# main.net
KiCad netlist of a schematic drawn in Altium Designer
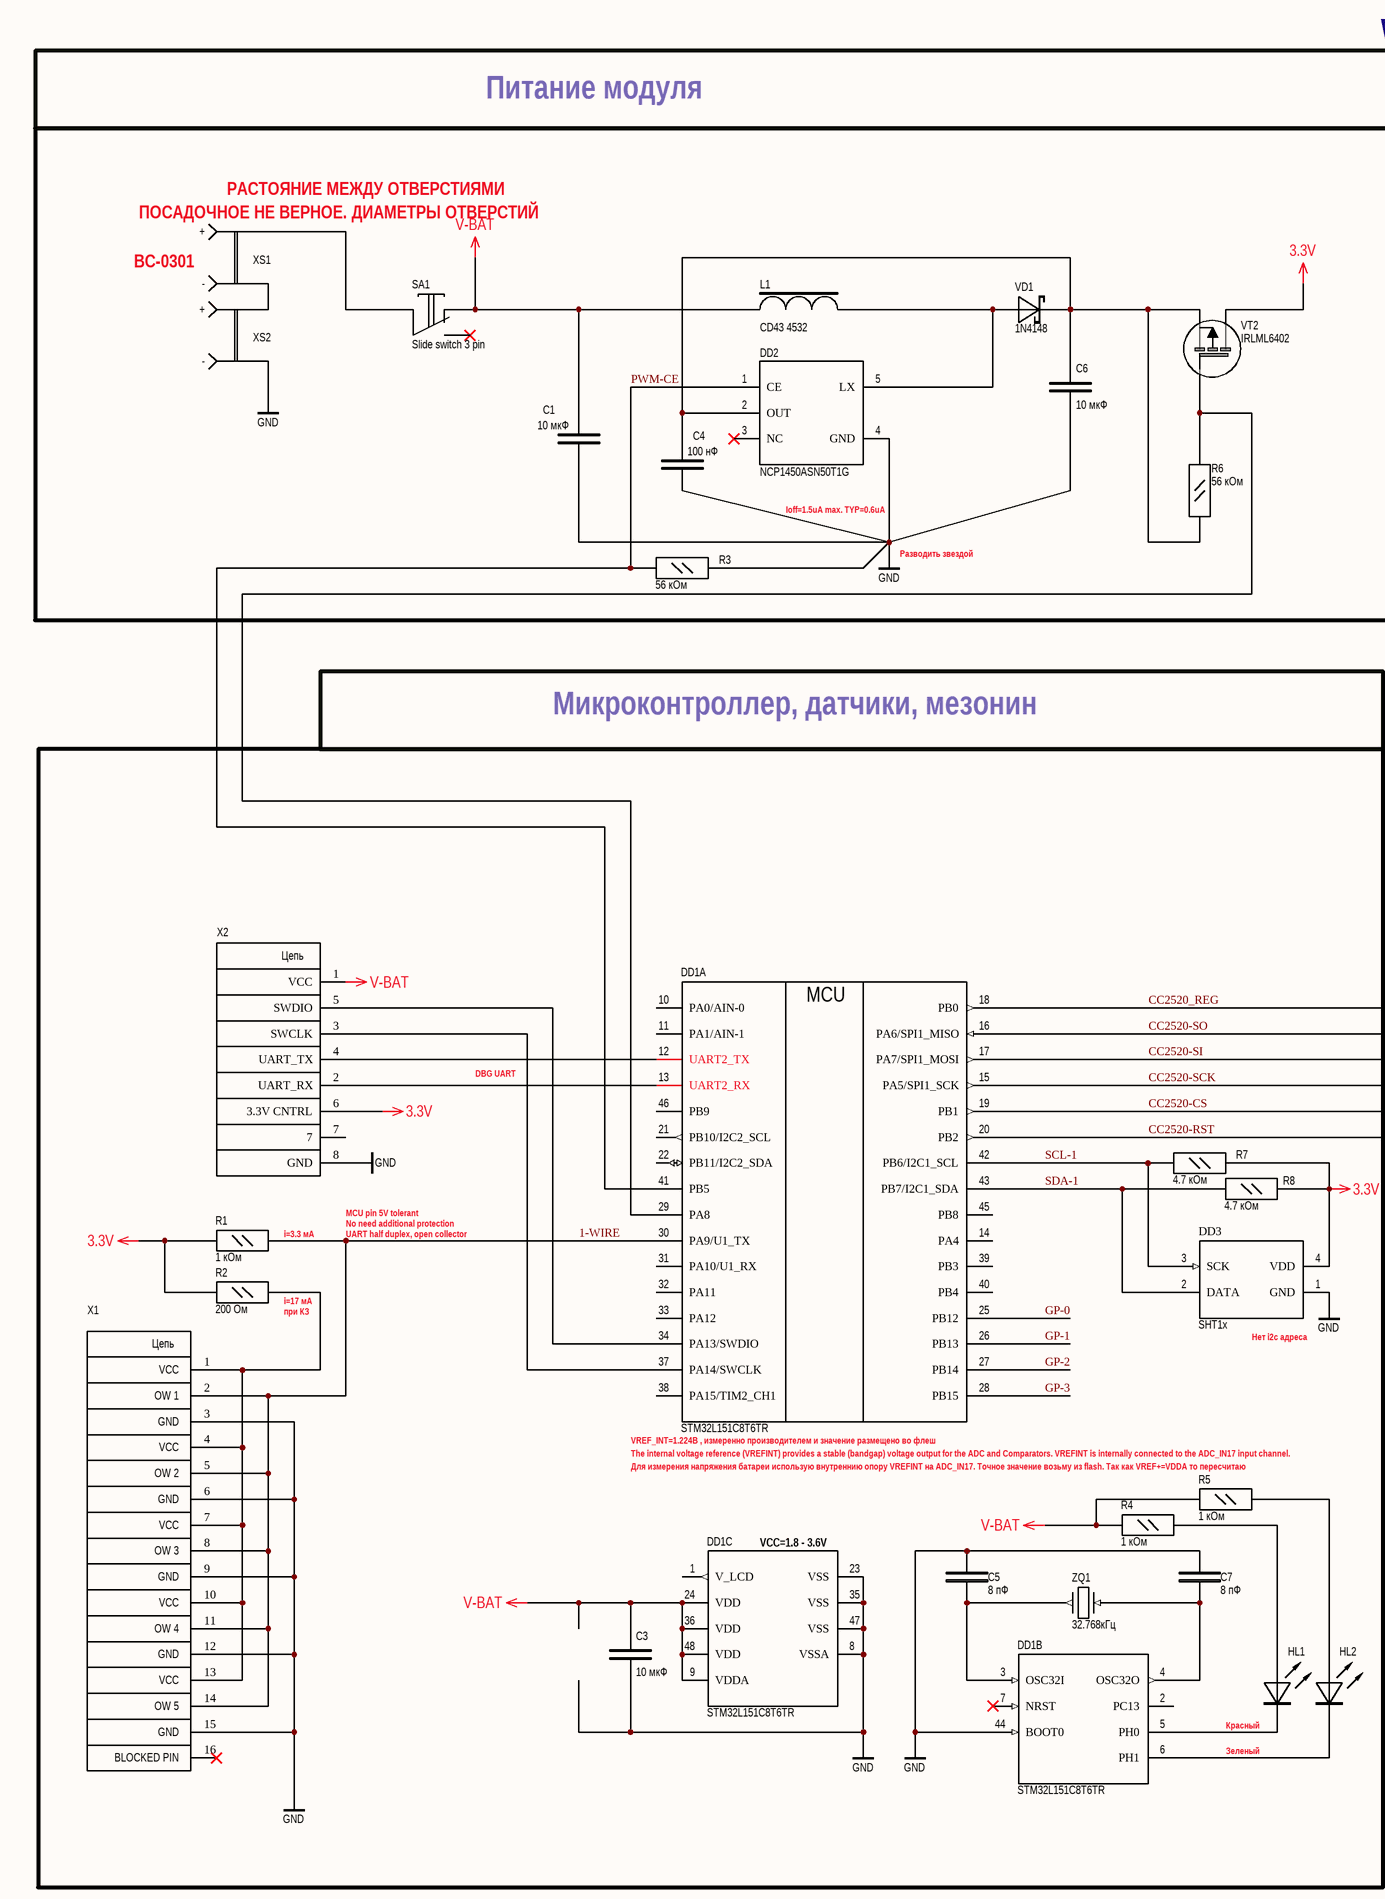
[diagram p0: main.SchDoc, left]
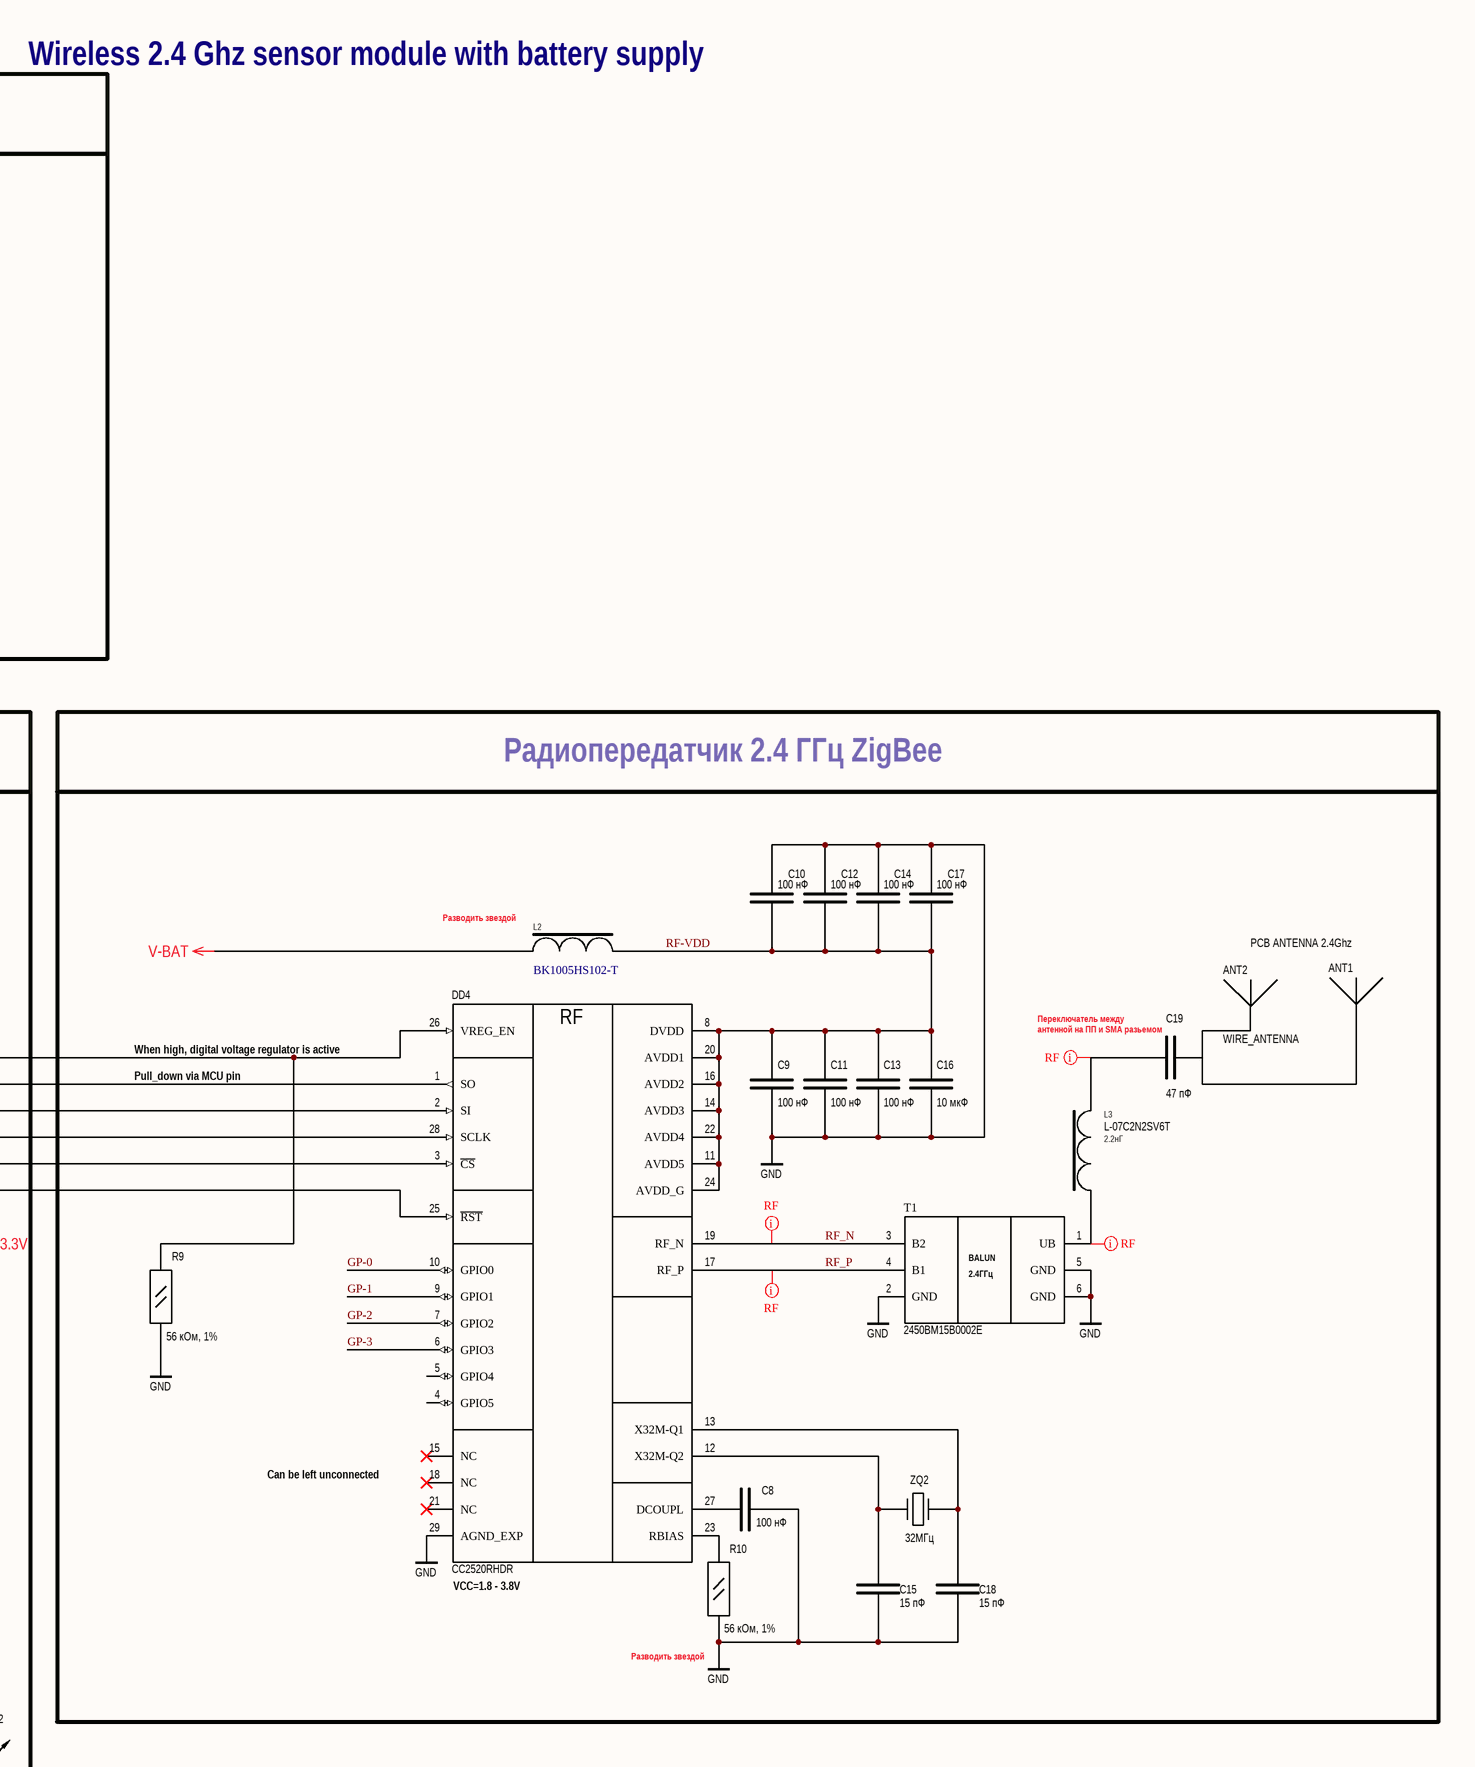
[diagram p1: main.SchDoc, right]

(export (version "E")
  (design (tool "Eeschema 10.0.6"))
  (components
    (comp (ref "ANT1")
      (value "PCB ANTENNA 2.4Ghz")
      (footprint "F-antena")
      (libsource (lib "Passive") (part "PCB ANTENNA 2.4Ghz"))
    )
    (comp (ref "ANT2")
      (value "WIRE_ANTENNA")
      (footprint "WIRED ANTENA 2.4GHz")
      (libsource (lib "Passive") (part "WIRE_ANTENNA"))
    )
    (comp (ref "C1") (value "10 мкФ") (footprint "CAP0805") (libsource (lib "Passive") (part "CAP0805")))
    (comp (ref "C3")
      (value "10 мкФ")
      (footprint "CAP0805")
      (description "Конденсатор")
      (libsource (lib "Passive") (part "CAP0805"))
    )
    (comp (ref "C4")
      (value "100 нФ")
      (footprint "CAP0402")
      (description "Конденсатор")
      (libsource (lib "Passive") (part "CAP0805"))
    )
    (comp (ref "C5")
      (value "8 пФ")
      (footprint "CAP0402")
      (description "Конденсатор")
      (libsource (lib "Passive") (part "CAP0805"))
    )
    (comp (ref "C6") (value "10 мкФ") (footprint "CAP0805") (libsource (lib "Passive") (part "CAP0805")))
    (comp (ref "C7")
      (value "8 пФ")
      (footprint "CAP0402")
      (description "Конденсатор")
      (libsource (lib "Passive") (part "CAP0805"))
    )
    (comp (ref "C8")
      (value "100 нФ")
      (footprint "CAP0402")
      (description "Конденсатор")
      (libsource (lib "") (part "CAP0805_2"))
    )
    (comp (ref "C9")
      (value "100 нФ")
      (footprint "CAP0402")
      (description "Конденсатор")
      (libsource (lib "Passive") (part "CAP0805"))
    )
    (comp (ref "C10")
      (value "100 нФ")
      (footprint "CAP0402")
      (description "Конденсатор")
      (libsource (lib "") (part "CAP0805_1"))
    )
    (comp (ref "C11")
      (value "100 нФ")
      (footprint "CAP0402")
      (description "Конденсатор")
      (libsource (lib "Passive") (part "CAP0805"))
    )
    (comp (ref "C12")
      (value "100 нФ")
      (footprint "CAP0402")
      (description "Конденсатор")
      (libsource (lib "") (part "CAP0805_1"))
    )
    (comp (ref "C13")
      (value "100 нФ")
      (footprint "CAP0402")
      (description "Конденсатор")
      (libsource (lib "Passive") (part "CAP0805"))
    )
    (comp (ref "C14")
      (value "100 нФ")
      (footprint "CAP0402")
      (description "Конденсатор")
      (libsource (lib "") (part "CAP0805_1"))
    )
    (comp (ref "C15")
      (value "15 пФ")
      (footprint "CAP0402")
      (description "Конденсатор")
      (libsource (lib "Passive") (part "CAP0805"))
    )
    (comp (ref "C16")
      (value "10 мкФ")
      (footprint "CAP0805")
      (description "Конденсатор")
      (libsource (lib "Passive") (part "CAP0805"))
    )
    (comp (ref "C17")
      (value "100 нФ")
      (footprint "CAP0402")
      (description "Конденсатор")
      (libsource (lib "") (part "CAP0805_1"))
    )
    (comp (ref "C18")
      (value "15 пФ")
      (footprint "CAP0402")
      (description "Конденсатор")
      (libsource (lib "Passive") (part "CAP0805"))
    )
    (comp (ref "C19")
      (value "47 пФ")
      (footprint "CAP0402 -  SWITCH")
      (libsource (lib "Passive") (part "CAP0402 SMD SWITCH"))
    )
    (comp (ref "DD1")
      (value "STM32L151C8T6TR")
      (footprint "LQFP-48")
      (description "Микроконтроллер")
      (libsource (lib "IC") (part "STM32L151C8T6TR"))
    )
    (comp (ref "DD2")
      (value "NCP1450ASN50T1G")
      (footprint "SOT-23-5")
      (description "Step Up PWM")
      (libsource (lib "IC") (part "NCP1400ASN33T1G"))
    )
    (comp (ref "DD3")
      (value "SHT1x")
      (footprint "SHT1x")
      (description "Датчик влажности/температуры")
      (libsource (lib "IC") (part "SHT1x"))
    )
    (comp (ref "DD4") (value "CC2520RHDR") (footprint "QFN28") (libsource (lib "IC") (part "CC2520RHDR")))
    (comp (ref "HL1")
      (value "LED")
      (footprint "KP-2012EC")
      (description "Светодиод красный")
      (libsource (lib "Semiconductor") (part "LED"))
    )
    (comp (ref "HL2")
      (value "LED")
      (footprint "KP-2012SGC")
      (description "Светодиод зеленый")
      (libsource (lib "Semiconductor") (part "LED"))
    )
    (comp (ref "L1")
      (value "CD43 4532")
      (footprint "CD43")
      (description "Дросель")
      (libsource (lib "Passive") (part "CD43 4532"))
    )
    (comp (ref "L2")
      (value "BK1005HS102-T")
      (footprint "IND0402")
      (description "Дросель")
      (libsource (lib "Passive") (part "BK1005HS102-T"))
    )
    (comp (ref "L3")
      (value "L-07C2N2SV6T")
      (footprint "CAP0402")
      (description "Дросель высокочастотный")
      (fields (field (name "ALTIUM_VALUE") "2.2нГ"))
      (libsource (lib "Passive") (part "L-07C2N2SV6T"))
    )
    (comp (ref "R1")
      (value "1 кОм")
      (footprint "RES0402")
      (description "Резистор 0805")
      (fields (field (name "Comment") "RES0805"))
      (libsource (lib "Passive") (part "RES0805"))
    )
    (comp (ref "R2")
      (value "200 Ом")
      (footprint "RES0402")
      (description "Резистор 0805")
      (fields (field (name "Comment") "RES0805"))
      (libsource (lib "Passive") (part "RES0805"))
    )
    (comp (ref "R3")
      (value "56 кОм")
      (footprint "RES0402")
      (description "Резистор 0805")
      (fields (field (name "Comment") "RES0805"))
      (libsource (lib "Passive") (part "RES0805"))
    )
    (comp (ref "R4")
      (value "1 кОм")
      (footprint "RES0402")
      (description "Резистор 0805")
      (fields (field (name "Comment") "RES0805"))
      (libsource (lib "Passive") (part "RES0805"))
    )
    (comp (ref "R5")
      (value "1 кОм")
      (footprint "RES0402")
      (description "Резистор 0805")
      (fields (field (name "Comment") "RES0805"))
      (libsource (lib "Passive") (part "RES0805"))
    )
    (comp (ref "R6")
      (value "56 кОм")
      (footprint "RES0402")
      (description "Резистор 0805")
      (fields (field (name "Comment") "RES0805"))
      (libsource (lib "Passive") (part "RES0805"))
    )
    (comp (ref "R7")
      (value "4.7 кОм")
      (footprint "RES0402")
      (description "Резистор 0805")
      (fields (field (name "Comment") "RES0805"))
      (libsource (lib "Passive") (part "RES0805"))
    )
    (comp (ref "R8")
      (value "4.7 кОм")
      (footprint "RES0402")
      (description "Резистор 0805")
      (fields (field (name "Comment") "RES0805"))
      (libsource (lib "Passive") (part "RES0805"))
    )
    (comp (ref "R9")
      (value "56 кОм, 1%")
      (footprint "RES0402")
      (description "Резистор 0805")
      (fields (field (name "Comment") "RES0805"))
      (libsource (lib "Passive") (part "RES0805"))
    )
    (comp (ref "R10")
      (value "56 кОм, 1%")
      (footprint "RES0402")
      (description "Резистор 0805")
      (fields (field (name "Comment") "RES0805"))
      (libsource (lib "Passive") (part "RES0805"))
    )
    (comp (ref "SA1")
      (value "Slide switch 3 pin")
      (footprint "L-KLS7-SS-12F19-G5")
      (libsource (lib "Connectors") (part "L-KLS7-SS-12F19-G5"))
    )
    (comp (ref "T1")
      (value "2450BM15B0002E")
      (footprint "2450BM15B0002")
      (libsource (lib "Passive") (part "2450BM15B0002E"))
    )
    (comp (ref "VD1")
      (value "1N4148")
      (footprint "SOD-123")
      (description "Диод Шотки")
      (libsource (lib "Semiconductor") (part "1N4148"))
    )
    (comp (ref "VT2")
      (value "IRLML6402")
      (footprint "SOT-23-3")
      (description "p-mosfet   -20V 3.7A")
      (libsource (lib "Semiconductor") (part "IRLML6402"))
    )
    (comp (ref "X1") (value "?") (footprint "IDC-16MR") (libsource (lib "Connectors") (part "IDC-16-MR")))
    (comp (ref "X2")
      (value "?")
      (footprint "PBD-08 - POGO PIN")
      (libsource (lib "Connectors") (part "Разьем_8_под_pogopin"))
    )
    (comp (ref "XS1")
      (value "Топология ПП")
      (footprint "KEYSTONE AA CLIPS")
      (description "Напаеваемые держатели для батарей АА на ПП")
      (libsource (lib "Connectors") (part "Battery AA Clips on PCB"))
    )
    (comp (ref "XS2")
      (value "Топология ПП")
      (footprint "KEYSTONE AA CLIPS")
      (description "Напаеваемые держатели для батарей АА на ПП")
      (libsource (lib "Connectors") (part "Battery AA Clips on PCB"))
    )
    (comp (ref "ZQ1")
      (value "32.768кГц")
      (footprint "Crystal_1")
      (description "Кварцевый резонатор")
      (libsource (lib "Generators") (part "32.768 кГц"))
    )
    (comp (ref "ZQ2")
      (value "32МГц")
      (footprint "HC49/S")
      (description "Кварцевый резонатор")
      (libsource (lib "Generators") (part "HC-49S 32МГц"))
    )
  )
  (nets
    (net (code "1") (name "/1-WIRE") (class "Default")
      (node (ref "DD1") (pin "30") (pinfunction "PA9/U1_TX_30") (pintype "open_collector"))
      (node (ref "R1") (pin "1") (pintype "passive"))
      (node (ref "X1") (pin "11") (pinfunction "OW_4_11") (pintype "passive"))
      (node (ref "X1") (pin "14") (pinfunction "OW_5_14") (pintype "passive"))
      (node (ref "X1") (pin "2") (pinfunction "OW_1_2") (pintype "passive"))
      (node (ref "X1") (pin "5") (pinfunction "OW_2_5") (pintype "passive"))
      (node (ref "X1") (pin "8") (pinfunction "OW_3_8") (pintype "passive"))
    )
    (net (code "2") (name "/CC2520-CS") (class "Default")
      (node (ref "DD1") (pin "19") (pinfunction "PB1_19") (pintype "output"))
      (node (ref "DD4") (pin "3") (pinfunction "~{CS}_3") (pintype "input"))
    )
    (net (code "3") (name "/CC2520-RST") (class "Default")
      (node (ref "DD1") (pin "20") (pinfunction "PB2_20") (pintype "output"))
      (node (ref "DD4") (pin "25") (pinfunction "~{RST}_25") (pintype "input"))
    )
    (net (code "4") (name "/CC2520-SCK") (class "Default")
      (node (ref "DD1") (pin "15") (pinfunction "PA5/SPI1_SCK_15") (pintype "output"))
      (node (ref "DD4") (pin "28") (pinfunction "SCLK_28") (pintype "input"))
    )
    (net (code "5") (name "/CC2520-SI") (class "Default")
      (node (ref "DD1") (pin "17") (pinfunction "PA7/SPI1_MOSI_17") (pintype "output"))
      (node (ref "DD4") (pin "2") (pinfunction "SI_2") (pintype "input"))
    )
    (net (code "6") (name "/CC2520-SO") (class "Default")
      (node (ref "DD1") (pin "16") (pinfunction "PA6/SPI1_MISO_16") (pintype "input"))
      (node (ref "DD4") (pin "1") (pinfunction "SO_1") (pintype "output"))
    )
    (net (code "7") (name "/CC2520_REG") (class "Default")
      (node (ref "DD1") (pin "18") (pinfunction "PB0_18") (pintype "output"))
      (node (ref "DD4") (pin "26") (pinfunction "VREG_EN_26") (pintype "input"))
      (node (ref "R9") (pin "2") (pintype "passive"))
    )
    (net (code "8") (name "/GP-0") (class "Default")
      (node (ref "DD1") (pin "25") (pinfunction "PB12_25") (pintype "passive"))
      (node (ref "DD4") (pin "10") (pinfunction "GPIO0_10") (pintype "bidirectional"))
    )
    (net (code "9") (name "/GP-1") (class "Default")
      (node (ref "DD1") (pin "26") (pinfunction "PB13_26") (pintype "passive"))
      (node (ref "DD4") (pin "9") (pinfunction "GPIO1_9") (pintype "bidirectional"))
    )
    (net (code "10") (name "/GP-2") (class "Default")
      (node (ref "DD1") (pin "27") (pinfunction "PB14_27") (pintype "passive"))
      (node (ref "DD4") (pin "7") (pinfunction "GPIO2_7") (pintype "bidirectional"))
    )
    (net (code "11") (name "/GP-3") (class "Default")
      (node (ref "DD1") (pin "28") (pinfunction "PB15_28") (pintype "passive"))
      (node (ref "DD4") (pin "6") (pinfunction "GPIO3_6") (pintype "bidirectional"))
    )
    (net (code "12") (name "/PWM-CE") (class "Default")
      (node (ref "DD1") (pin "41") (pinfunction "PB5_41") (pintype "passive"))
      (node (ref "DD2") (pin "1") (pinfunction "CE_1") (pintype "passive"))
      (node (ref "R3") (pin "2") (pintype "passive"))
    )
    (net (code "13") (name "/RF-VDD") (class "Default")
      (node (ref "C10") (pin "2") (pinfunction "2_2") (pintype "passive"))
      (node (ref "C11") (pin "2") (pinfunction "2_2") (pintype "passive"))
      (node (ref "C12") (pin "2") (pinfunction "2_2") (pintype "passive"))
      (node (ref "C13") (pin "2") (pinfunction "2_2") (pintype "passive"))
      (node (ref "C14") (pin "2") (pinfunction "2_2") (pintype "passive"))
      (node (ref "C16") (pin "2") (pinfunction "2_2") (pintype "passive"))
      (node (ref "C17") (pin "2") (pinfunction "2_2") (pintype "passive"))
      (node (ref "C9") (pin "2") (pinfunction "2_2") (pintype "passive"))
      (node (ref "DD4") (pin "11") (pinfunction "AVDD5_11") (pintype "power_in"))
      (node (ref "DD4") (pin "14") (pinfunction "AVDD3_14") (pintype "power_in"))
      (node (ref "DD4") (pin "16") (pinfunction "AVDD2_16") (pintype "power_in"))
      (node (ref "DD4") (pin "20") (pinfunction "AVDD1_20") (pintype "power_in"))
      (node (ref "DD4") (pin "22") (pinfunction "AVDD4_22") (pintype "power_in"))
      (node (ref "DD4") (pin "24") (pinfunction "AVDD_G_24") (pintype "power_in"))
      (node (ref "DD4") (pin "8") (pinfunction "DVDD_8") (pintype "power_in"))
      (node (ref "L2") (pin "2") (pinfunction "2_2") (pintype "passive"))
    )
    (net (code "14") (name "/RF_N") (class "Default")
      (node (ref "DD4") (pin "19") (pinfunction "RF_N_19") (pintype "passive"))
      (node (ref "T1") (pin "3") (pinfunction "B2_3") (pintype "passive"))
    )
    (net (code "15") (name "/RF_P") (class "Default")
      (node (ref "DD4") (pin "17") (pinfunction "RF_P_17") (pintype "passive"))
      (node (ref "T1") (pin "4") (pinfunction "B1_4") (pintype "passive"))
    )
    (net (code "16") (name "/SCL-1") (class "Default")
      (node (ref "DD1") (pin "42") (pinfunction "PB6/I2C1_SCL_42") (pintype "open_collector"))
      (node (ref "DD3") (pin "3") (pinfunction "SCK_3") (pintype "input"))
      (node (ref "R7") (pin "2") (pintype "passive"))
    )
    (net (code "17") (name "/SDA-1") (class "Default")
      (node (ref "DD1") (pin "43") (pinfunction "PB7/I2C1_SDA_43") (pintype "open_collector"))
      (node (ref "DD3") (pin "2") (pinfunction "DATA_2") (pintype "passive"))
      (node (ref "R8") (pin "2") (pintype "passive"))
    )
    (net (code "18") (name "3.3V") (class "Default")
      (node (ref "DD3") (pin "4") (pinfunction "VDD_4") (pintype "passive"))
      (node (ref "R1") (pin "2") (pintype "passive"))
      (node (ref "R2") (pin "2") (pintype "passive"))
      (node (ref "R7") (pin "1") (pintype "passive"))
      (node (ref "R8") (pin "1") (pintype "passive"))
      (node (ref "VT2") (pin "D") (pinfunction "Drain_D") (pintype "passive"))
      (node (ref "X2") (pin "6") (pinfunction "3.3V_CNTRL_6") (pintype "passive"))
    )
    (net (code "19") (name "GND") (class "Default")
      (node (ref "C1") (pin "1") (pinfunction "1_1") (pintype "passive"))
      (node (ref "C10") (pin "1") (pinfunction "1_1") (pintype "passive"))
      (node (ref "C11") (pin "1") (pinfunction "1_1") (pintype "passive"))
      (node (ref "C12") (pin "1") (pinfunction "1_1") (pintype "passive"))
      (node (ref "C13") (pin "1") (pinfunction "1_1") (pintype "passive"))
      (node (ref "C14") (pin "1") (pinfunction "1_1") (pintype "passive"))
      (node (ref "C15") (pin "1") (pinfunction "1_1") (pintype "passive"))
      (node (ref "C16") (pin "1") (pinfunction "1_1") (pintype "passive"))
      (node (ref "C17") (pin "1") (pinfunction "1_1") (pintype "passive"))
      (node (ref "C18") (pin "1") (pinfunction "1_1") (pintype "passive"))
      (node (ref "C3") (pin "1") (pinfunction "1_1") (pintype "passive"))
      (node (ref "C4") (pin "1") (pinfunction "1_1") (pintype "passive"))
      (node (ref "C5") (pin "2") (pinfunction "2_2") (pintype "passive"))
      (node (ref "C6") (pin "1") (pinfunction "1_1") (pintype "passive"))
      (node (ref "C7") (pin "2") (pinfunction "2_2") (pintype "passive"))
      (node (ref "C8") (pin "2") (pinfunction "2_2") (pintype "passive"))
      (node (ref "C9") (pin "1") (pinfunction "1_1") (pintype "passive"))
      (node (ref "DD1") (pin "23") (pinfunction "VSS_23") (pintype "power_in"))
      (node (ref "DD1") (pin "35") (pinfunction "VSS_35") (pintype "power_in"))
      (node (ref "DD1") (pin "44") (pinfunction "BOOT0_44") (pintype "input"))
      (node (ref "DD1") (pin "47") (pinfunction "VSS_47") (pintype "power_in"))
      (node (ref "DD1") (pin "8") (pinfunction "VSSA_8") (pintype "power_in"))
      (node (ref "DD2") (pin "4") (pinfunction "GND_4") (pintype "passive"))
      (node (ref "DD3") (pin "1") (pinfunction "GND_1") (pintype "passive"))
      (node (ref "DD4") (pin "29") (pinfunction "AGND_EXP_29") (pintype "power_in"))
      (node (ref "R10") (pin "1") (pintype "passive"))
      (node (ref "R3") (pin "1") (pintype "passive"))
      (node (ref "R9") (pin "1") (pintype "passive"))
      (node (ref "T1") (pin "2") (pinfunction "GND_2") (pintype "passive"))
      (node (ref "T1") (pin "5") (pinfunction "GND_5") (pintype "passive"))
      (node (ref "T1") (pin "6") (pinfunction "GND_6") (pintype "passive"))
      (node (ref "X1") (pin "12") (pinfunction "GND_12") (pintype "passive"))
      (node (ref "X1") (pin "15") (pinfunction "GND_15") (pintype "passive"))
      (node (ref "X1") (pin "3") (pinfunction "GND_3") (pintype "passive"))
      (node (ref "X1") (pin "6") (pinfunction "GND_6") (pintype "passive"))
      (node (ref "X1") (pin "9") (pinfunction "GND_9") (pintype "passive"))
      (node (ref "X2") (pin "8") (pinfunction "GND_8") (pintype "passive"))
      (node (ref "XS2") (pin "2") (pinfunction "-_2") (pintype "passive"))
    )
    (net (code "20") (name "Net-(ANT1-Pad0)") (class "Default")
      (node (ref "ANT1") (pin "0") (pinfunction "0_0") (pintype "passive"))
      (node (ref "C19") (pin "3") (pinfunction "3_3") (pintype "passive"))
    )
    (net (code "21") (name "Net-(ANT2-0)") (class "Default")
      (node (ref "ANT2") (pin "1") (pinfunction "0_1") (pintype "passive"))
      (node (ref "C19") (pin "2") (pinfunction "2_2") (pintype "passive"))
    )
    (net (code "22") (name "Net-(C19-Pad1)") (class "Default")
      (node (ref "C19") (pin "1") (pinfunction "1_1") (pintype "passive"))
      (node (ref "L3") (pin "2") (pinfunction "2_2") (pintype "passive"))
    )
    (net (code "23") (name "Net-(DD1A-PA8)") (class "Default")
      (node (ref "DD1") (pin "29") (pinfunction "PA8_29") (pintype "passive"))
      (node (ref "R6") (pin "1") (pintype "passive"))
      (node (ref "VT2") (pin "G") (pinfunction "Gate_G") (pintype "passive"))
    )
    (net (code "24") (name "Net-(DD1A-PA13{slash}SWDIO)") (class "Default")
      (node (ref "DD1") (pin "34") (pinfunction "PA13/SWDIO_34") (pintype "passive"))
      (node (ref "X2") (pin "5") (pinfunction "SWDIO_5") (pintype "passive"))
    )
    (net (code "25") (name "Net-(DD1A-PA14{slash}SWCLK)") (class "Default")
      (node (ref "DD1") (pin "37") (pinfunction "PA14/SWCLK_37") (pintype "passive"))
      (node (ref "X2") (pin "3") (pinfunction "SWCLK_3") (pintype "passive"))
    )
    (net (code "26") (name "Net-(DD1A-UART2_RX)") (class "Default")
      (node (ref "DD1") (pin "13") (pinfunction "UART2_RX_13") (pintype "passive"))
      (node (ref "X2") (pin "2") (pinfunction "UART_RX_2") (pintype "passive"))
    )
    (net (code "27") (name "Net-(DD1A-UART2_TX)") (class "Default")
      (node (ref "DD1") (pin "12") (pinfunction "UART2_TX_12") (pintype "passive"))
      (node (ref "X2") (pin "4") (pinfunction "UART_TX_4") (pintype "passive"))
    )
    (net (code "28") (name "Net-(DD1B-OSC32I)") (class "Default")
      (node (ref "C5") (pin "1") (pinfunction "1_1") (pintype "passive"))
      (node (ref "DD1") (pin "3") (pinfunction "OSC32I_3") (pintype "input"))
      (node (ref "ZQ1") (pin "1") (pinfunction "1_1") (pintype "output"))
    )
    (net (code "29") (name "Net-(DD1B-OSC32O)") (class "Default")
      (node (ref "C7") (pin "1") (pinfunction "1_1") (pintype "passive"))
      (node (ref "DD1") (pin "4") (pinfunction "OSC32O_4") (pintype "output"))
      (node (ref "ZQ1") (pin "2") (pinfunction "2_2") (pintype "input"))
    )
    (net (code "30") (name "Net-(DD1B-PH0)") (class "Default")
      (node (ref "DD1") (pin "5") (pinfunction "PH0_5") (pintype "open_collector"))
      (node (ref "HL1") (pin "C") (pinfunction "Cathode_C") (pintype "passive"))
    )
    (net (code "31") (name "Net-(DD1B-PH1)") (class "Default")
      (node (ref "DD1") (pin "6") (pinfunction "PH1_6") (pintype "open_collector"))
      (node (ref "HL2") (pin "C") (pinfunction "Cathode_C") (pintype "passive"))
    )
    (net (code "32") (name "Net-(DD2-LX)") (class "Default")
      (node (ref "DD2") (pin "5") (pinfunction "LX_5") (pintype "passive"))
      (node (ref "L1") (pin "2") (pinfunction "2_2") (pintype "passive"))
      (node (ref "VD1") (pin "A") (pinfunction "Anode_A") (pintype "passive"))
    )
    (net (code "33") (name "Net-(DD2-OUT)") (class "Default")
      (node (ref "C4") (pin "2") (pinfunction "2_2") (pintype "passive"))
      (node (ref "C6") (pin "2") (pinfunction "2_2") (pintype "passive"))
      (node (ref "DD2") (pin "2") (pinfunction "OUT_2") (pintype "passive"))
      (node (ref "R6") (pin "2") (pintype "passive"))
      (node (ref "VD1") (pin "C") (pinfunction "Cathode_C") (pintype "passive"))
      (node (ref "VT2") (pin "S") (pinfunction "Source_S") (pintype "passive"))
    )
    (net (code "34") (name "Net-(DD4-DCOUPL)") (class "Default")
      (node (ref "C8") (pin "1") (pinfunction "1_1") (pintype "passive"))
      (node (ref "DD4") (pin "27") (pinfunction "DCOUPL_27") (pintype "passive"))
    )
    (net (code "35") (name "Net-(DD4-RBIAS)") (class "Default")
      (node (ref "DD4") (pin "23") (pinfunction "RBIAS_23") (pintype "passive"))
      (node (ref "R10") (pin "2") (pintype "passive"))
    )
    (net (code "36") (name "Net-(DD4-X32M-Q1)") (class "Default")
      (node (ref "C18") (pin "2") (pinfunction "2_2") (pintype "passive"))
      (node (ref "DD4") (pin "13") (pinfunction "X32M-Q1_13") (pintype "passive"))
      (node (ref "ZQ2") (pin "1") (pinfunction "1_1") (pintype "passive"))
    )
    (net (code "37") (name "Net-(DD4-X32M-Q2)") (class "Default")
      (node (ref "C15") (pin "2") (pinfunction "2_2") (pintype "passive"))
      (node (ref "DD4") (pin "12") (pinfunction "X32M-Q2_12") (pintype "passive"))
      (node (ref "ZQ2") (pin "2") (pinfunction "2_2") (pintype "passive"))
    )
    (net (code "38") (name "Net-(HL1-Anode)") (class "Default")
      (node (ref "HL1") (pin "A") (pinfunction "Anode_A") (pintype "passive"))
      (node (ref "R4") (pin "1") (pintype "passive"))
    )
    (net (code "39") (name "Net-(HL2-Anode)") (class "Default")
      (node (ref "HL2") (pin "A") (pinfunction "Anode_A") (pintype "passive"))
      (node (ref "R5") (pin "1") (pintype "passive"))
    )
    (net (code "40") (name "Net-(R2-Pad1)") (class "Default")
      (node (ref "R2") (pin "1") (pintype "passive"))
      (node (ref "X1") (pin "1") (pinfunction "VCC_1") (pintype "passive"))
      (node (ref "X1") (pin "10") (pinfunction "VCC_10") (pintype "passive"))
      (node (ref "X1") (pin "13") (pinfunction "VCC_13") (pintype "passive"))
      (node (ref "X1") (pin "4") (pinfunction "VCC_4") (pintype "passive"))
      (node (ref "X1") (pin "7") (pinfunction "VCC_7") (pintype "passive"))
    )
    (net (code "41") (name "Net-(T1-UB)") (class "Default")
      (node (ref "L3") (pin "1") (pinfunction "1_1") (pintype "passive"))
      (node (ref "T1") (pin "1") (pinfunction "UB_1") (pintype "passive"))
    )
    (net (code "42") (name "Net-(XS1-+)") (class "Default")
      (node (ref "SA1") (pin "2") (pinfunction "2_2") (pintype "passive"))
      (node (ref "XS1") (pin "1") (pinfunction "+_1") (pintype "passive"))
    )
    (net (code "43") (name "Net-(XS1--)") (class "Default")
      (node (ref "XS1") (pin "2") (pinfunction "-_2") (pintype "passive"))
      (node (ref "XS2") (pin "1") (pinfunction "+_1") (pintype "passive"))
    )
    (net (code "44") (name "V-BAT") (class "Default")
      (node (ref "C1") (pin "2") (pinfunction "2_2") (pintype "passive"))
      (node (ref "C3") (pin "2") (pinfunction "2_2") (pintype "passive"))
      (node (ref "DD1") (pin "24") (pinfunction "VDD_24") (pintype "power_in"))
      (node (ref "DD1") (pin "36") (pinfunction "VDD_36") (pintype "power_in"))
      (node (ref "DD1") (pin "48") (pinfunction "VDD_48") (pintype "power_in"))
      (node (ref "DD1") (pin "9") (pinfunction "VDDA_9") (pintype "power_in"))
      (node (ref "L1") (pin "1") (pinfunction "1_1") (pintype "passive"))
      (node (ref "L2") (pin "1") (pinfunction "1_1") (pintype "passive"))
      (node (ref "R4") (pin "2") (pintype "passive"))
      (node (ref "R5") (pin "2") (pintype "passive"))
      (node (ref "SA1") (pin "1") (pinfunction "1_1") (pintype "passive"))
      (node (ref "X2") (pin "1") (pinfunction "VCC_1") (pintype "passive"))
    )
    (net (code "45") (name "unconnected-(DD1A-PA0{slash}AIN-0-Pad10)") (class "Default")
      (node (ref "DD1") (pin "10") (pinfunction "PA0/AIN-0_10") (pintype "passive"))
    )
    (net (code "46") (name "unconnected-(DD1A-PA1{slash}AIN-1-Pad11)") (class "Default")
      (node (ref "DD1") (pin "11") (pinfunction "PA1/AIN-1_11") (pintype "passive"))
    )
    (net (code "47") (name "unconnected-(DD1A-PA4-Pad14)") (class "Default")
      (node (ref "DD1") (pin "14") (pinfunction "PA4_14") (pintype "passive"))
    )
    (net (code "48") (name "unconnected-(DD1A-PA10{slash}U1_RX-Pad31)") (class "Default")
      (node (ref "DD1") (pin "31") (pinfunction "PA10/U1_RX_31") (pintype "passive"))
    )
    (net (code "49") (name "unconnected-(DD1A-PA11-Pad32)") (class "Default")
      (node (ref "DD1") (pin "32") (pinfunction "PA11_32") (pintype "passive"))
    )
    (net (code "50") (name "unconnected-(DD1A-PA12-Pad33)") (class "Default")
      (node (ref "DD1") (pin "33") (pinfunction "PA12_33") (pintype "passive"))
    )
    (net (code "51") (name "unconnected-(DD1A-PA15{slash}TIM2_CH1-Pad38)") (class "Default")
      (node (ref "DD1") (pin "38") (pinfunction "PA15/TIM2_CH1_38") (pintype "passive"))
    )
    (net (code "52") (name "unconnected-(DD1A-PB3-Pad39)") (class "Default")
      (node (ref "DD1") (pin "39") (pinfunction "PB3_39") (pintype "passive"))
    )
    (net (code "53") (name "unconnected-(DD1A-PB4-Pad40)") (class "Default")
      (node (ref "DD1") (pin "40") (pinfunction "PB4_40") (pintype "passive"))
    )
    (net (code "54") (name "unconnected-(DD1A-PB8-Pad45)") (class "Default")
      (node (ref "DD1") (pin "45") (pinfunction "PB8_45") (pintype "passive"))
    )
    (net (code "55") (name "unconnected-(DD1A-PB9-Pad46)") (class "Default")
      (node (ref "DD1") (pin "46") (pinfunction "PB9_46") (pintype "open_collector"))
    )
    (net (code "56") (name "unconnected-(DD1A-PB10{slash}I2C2_SCL-Pad21)") (class "Default")
      (node (ref "DD1") (pin "21") (pinfunction "PB10/I2C2_SCL_21") (pintype "output"))
    )
    (net (code "57") (name "unconnected-(DD1A-PB11{slash}I2C2_SDA-Pad22)") (class "Default")
      (node (ref "DD1") (pin "22") (pinfunction "PB11/I2C2_SDA_22") (pintype "bidirectional"))
    )
    (net (code "58") (name "unconnected-(DD1B-NRST-Pad7)") (class "Default")
      (node (ref "DD1") (pin "7") (pinfunction "NRST_7") (pintype "input+no_connect"))
    )
    (net (code "59") (name "unconnected-(DD1B-PC13-Pad2)") (class "Default")
      (node (ref "DD1") (pin "2") (pinfunction "PC13_2") (pintype "passive"))
    )
    (net (code "60") (name "unconnected-(DD1C-V_LCD-Pad1)") (class "Default")
      (node (ref "DD1") (pin "1") (pinfunction "V_LCD_1") (pintype "output"))
    )
    (net (code "61") (name "unconnected-(DD2-NC-Pad3)") (class "Default")
      (node (ref "DD2") (pin "3") (pinfunction "NC_3") (pintype "passive+no_connect"))
    )
    (net (code "62") (name "unconnected-(DD4-GPIO4-Pad5)") (class "Default")
      (node (ref "DD4") (pin "5") (pinfunction "GPIO4_5") (pintype "bidirectional"))
    )
    (net (code "63") (name "unconnected-(DD4-GPIO5-Pad4)") (class "Default")
      (node (ref "DD4") (pin "4") (pinfunction "GPIO5_4") (pintype "bidirectional"))
    )
    (net (code "64") (name "unconnected-(DD4-NC-Pad15)") (class "Default")
      (node (ref "DD4") (pin "15") (pinfunction "NC_15") (pintype "passive+no_connect"))
    )
    (net (code "65") (name "unconnected-(DD4-NC-Pad18)") (class "Default")
      (node (ref "DD4") (pin "18") (pinfunction "NC_18") (pintype "passive+no_connect"))
    )
    (net (code "66") (name "unconnected-(DD4-NC-Pad21)") (class "Default")
      (node (ref "DD4") (pin "21") (pinfunction "NC_21") (pintype "passive+no_connect"))
    )
    (net (code "67") (name "unconnected-(SA1-Pad3)") (class "Default")
      (node (ref "SA1") (pin "3") (pinfunction "3_3") (pintype "passive+no_connect"))
    )
    (net (code "68") (name "unconnected-(X1-BLOCKED_PIN-Pad16)") (class "Default")
      (node (ref "X1") (pin "16") (pinfunction "BLOCKED_PIN_16") (pintype "passive+no_connect"))
    )
    (net (code "69") (name "unconnected-(X2-Pad7)") (class "Default")
      (node (ref "X2") (pin "7") (pinfunction "7_7") (pintype "passive"))
    )
  )
)
